# DAC_To_LP_Filter.net
KiCad netlist of a schematic drawn in Altium Designer
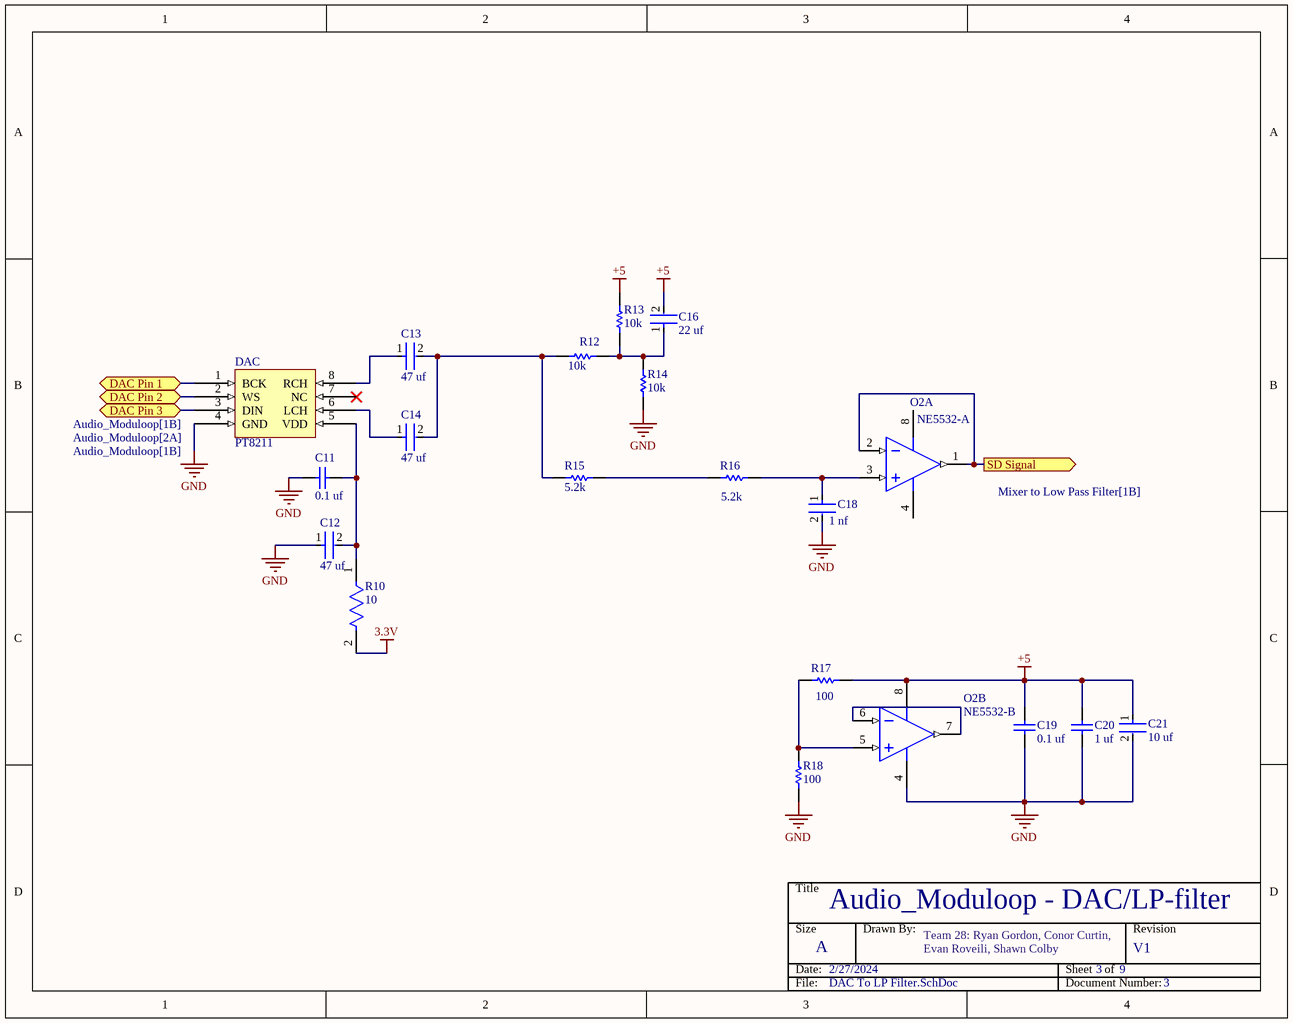
[diagram p0: DAC To LP Filter.SchDoc]

(export (version "E")
  (design (tool "Eeschema 10.0.6"))
  (components
    (comp (ref "C11")
      (value "0.1 uf")
      (footprint "VISH-K104K15X7RF5TL2")
      (description "Ceramic Capacitor, 100 nF, +/- 10%, 50 V, -55 to 125 degC, 2-Pin THD, RoHS, Tape and Reel")
      (fields (field (name "MANUFACTURER") "Vishay") (field (name "TOLERANCE") "±10%"))
      (libsource (lib "Altium Content Vault") (part "CAP-NP-2"))
    )
    (comp (ref "C12")
      (value "47 uf")
      (footprint "FP-RCE2A2-MFG")
      (description "Cap Ceramic 4.7uF 25V X7R ±10% Radial 2.5mm +125°C Automotive Ammo Pack")
      (fields (field (name "TOLERANCE") "10%"))
      (libsource (lib "Altium Content Vault") (part "b4654b650e69147ec39a6b967a45e02"))
    )
    (comp (ref "C13")
      (value "47 uf")
      (footprint "FP-RCE2A2-MFG")
      (description "Cap Ceramic 4.7uF 25V X7R ±10% Radial 2.5mm +125°C Automotive Ammo Pack")
      (fields (field (name "TOLERANCE") "10%"))
      (libsource (lib "Altium Content Vault") (part "b4654b650e69147ec39a6b967a45e02"))
    )
    (comp (ref "C14")
      (value "47 uf")
      (footprint "FP-RCE2A2-MFG")
      (description "Cap Ceramic 4.7uF 25V X7R ±10% Radial 2.5mm +125°C Automotive Ammo Pack")
      (fields (field (name "TOLERANCE") "10%"))
      (libsource (lib "Altium Content Vault") (part "b4654b650e69147ec39a6b967a45e02"))
    )
    (comp (ref "C16")
      (value "22 uf")
      (footprint "FP-RCEWM1-MFG")
      (description "Cap Ceramic 22uF 25V X7R ±20% Radial 5mm +125°C Automotive Ammo Pack")
      (fields (field (name "TOLERANCE") "20%"))
      (libsource (lib "Altium Content Vault") (part "02cd4be3c70576c341d710602a673aa"))
    )
    (comp (ref "C18")
      (value "1 nf")
      (footprint "FP-RCE0DB-MFG")
      (description "Cap Ceramic 470pF 100V X7R ±10% Radial 2.5mm +125°C Ammo Pack")
      (fields (field (name "TOLERANCE") "10%"))
      (libsource (lib "Altium Content Vault") (part "b4654b650e69147ec39a6b967a45e02"))
    )
    (comp (ref "C19")
      (value "0.1 uf")
      (footprint "CAPC2013X135X45ML10T25")
      (description "Chip Capacitor, 0.1 uF, +/- 10%, 50 V, -55 to 125 degC, 0805 (2012 Metric), RoHS, Tape and Reel")
      (fields (field (name "VOLTAGE") "50V") (field (name "TOLERANCE") "10%"))
      (libsource (lib "Altium Content Vault") (part "CAP-NP-2"))
    )
    (comp (ref "C20")
      (value "1 uf")
      (footprint "CAPC2013X145X50LL20T25")
      (fields (field (name "MANUFACTURER") "Kemet") (field (name "PART NUMBER") "C0805C105K4PACTU"))
      (libsource (lib "Altium Content Vault") (part "CAP"))
    )
    (comp (ref "C21")
      (value "10 uf")
      (footprint "FP-C0805C-DG-MFG")
      (description "CAP CER 10UF 10V X5R 0805")
      (fields (field (name "TOLERANCE") "10%") (field (name "MANUFACTURER PART NUMBER") "C0805C106K8PACTU"))
      (libsource (lib "Altium Content Vault") (part "11868f565c42a9108669ba33697ecf6"))
    )
    (comp (ref "DAC")
      (value "PT8211")
      (footprint "SOIC127P602X173-8N")
      (libsource (lib "Ryamgordon") (part "DAC"))
    )
    (comp (ref "O2")
      (value "NE5532-A")
      (footprint "ONSC-SOIC-8-751-07_V")
      (fields (field (name "MANUFACTURER") "On Semiconductor") (field (name "PARTNUMBER") "NE5532AD8R2G"))
      (libsource (lib "Altium Content Vault") (part "ONSC-NE5532-SOIC-8-751-07"))
    )
    (comp (ref "R10")
      (value "10")
      (footprint "FP-RN732A-MFG")
      (description "SMD Chip Resistor, Thin Film, 10Ω, 100 V, 0805 [2012 Metric], 100 mW, 0.1%, RN73 Series")
      (fields
        (field (name "MANUFACTURER") "TE Connectivity")
        (field (name "MANUFACTURER PART NUMBER") "RN73C2A10RBTG")
      )
      (libsource (lib "Altium Content Vault") (part "1029c3af85768c4190bb7ad29bc67b5"))
    )
    (comp (ref "R12")
      (value "10k")
      (footprint "RESC2013X60X35NL10T20")
      (description "Chip Resistor, 10 KOhm, +/- 1%, 0.125 W, -55 to 155 degC, 0805 (2012 Metric), RoHS, Tape and Reel")
      (fields (field (name "MANUFACTURER") "Yageo"))
      (libsource (lib "Altium Content Vault") (part "RES-2"))
    )
    (comp (ref "R13")
      (value "10k")
      (footprint "RESC2013X60X35NL10T20")
      (description "Chip Resistor, 10 KOhm, +/- 1%, 0.125 W, -55 to 155 degC, 0805 (2012 Metric), RoHS, Tape and Reel")
      (fields (field (name "MANUFACTURER") "Yageo"))
      (libsource (lib "Altium Content Vault") (part "RES-2"))
    )
    (comp (ref "R14")
      (value "10k")
      (footprint "RESC2013X60X35NL10T20")
      (description "Chip Resistor, 10 KOhm, +/- 1%, 0.125 W, -55 to 155 degC, 0805 (2012 Metric), RoHS, Tape and Reel")
      (fields (field (name "MANUFACTURER") "Yageo"))
      (libsource (lib "Altium Content Vault") (part "RES-2"))
    )
    (comp (ref "R15")
      (value "5.2k")
      (footprint "RESC2013X70X40LL20T20")
      (fields (field (name "MANUFACTURER") "Panasonic") (field (name "PART NUMBER") "ERJ6ENF6801V"))
      (libsource (lib "Altium Content Vault") (part "RES"))
    )
    (comp (ref "R16")
      (value "5.2k")
      (footprint "RESC2013X70X40LL20T20")
      (fields (field (name "MANUFACTURER") "Panasonic") (field (name "PART NUMBER") "ERJ6ENF6801V"))
      (libsource (lib "Altium Content Vault") (part "RES"))
    )
    (comp (ref "R17")
      (value "100")
      (footprint "RESC2013X60X40ML20T25")
      (fields (field (name "MANUFACTURER") "Panasonic") (field (name "PART NUMBER") "ERA6AEB101V"))
      (libsource (lib "Altium Content Vault") (part "RES"))
    )
    (comp (ref "R18")
      (value "100")
      (footprint "RESC2013X60X40ML20T25")
      (fields (field (name "MANUFACTURER") "Panasonic") (field (name "PART NUMBER") "ERA6AEB101V"))
      (libsource (lib "Altium Content Vault") (part "RES"))
    )
  )
  (nets
    (net (code "1") (name "+5") (class "Default")
      (node (ref "C16") (pin "2") (pinfunction "2_2") (pintype "passive"))
      (node (ref "C19") (pin "1") (pinfunction "1_1") (pintype "passive"))
      (node (ref "C20") (pin "1") (pinfunction "1_1") (pintype "passive"))
      (node (ref "C21") (pin "1") (pinfunction "1_1") (pintype "passive"))
      (node (ref "O2") (pin "8") (pinfunction "V+_8") (pintype "power_in"))
      (node (ref "R13") (pin "1") (pinfunction "1_1") (pintype "passive"))
      (node (ref "R17") (pin "2") (pinfunction "2_2") (pintype "passive"))
    )
    (net (code "2") (name "/DAC Pin 1") (class "Default")
      (node (ref "DAC") (pin "1") (pinfunction "BCK_1") (pintype "input"))
    )
    (net (code "3") (name "/DAC Pin 2") (class "Default")
      (node (ref "DAC") (pin "2") (pinfunction "WS_2") (pintype "input"))
    )
    (net (code "4") (name "/DAC Pin 3") (class "Default")
      (node (ref "DAC") (pin "3") (pinfunction "DIN_3") (pintype "input"))
    )
    (net (code "5") (name "/SD Signal") (class "Default")
      (node (ref "O2") (pin "1") (pinfunction "OUTA_1") (pintype "output"))
      (node (ref "O2") (pin "2") (pinfunction "INA-_2") (pintype "input"))
    )
    (net (code "6") (name "3.3V") (class "Default")
      (node (ref "R10") (pin "2") (pinfunction "2_2") (pintype "passive"))
    )
    (net (code "7") (name "GND") (class "Default")
      (node (ref "C11") (pin "2") (pinfunction "2_2") (pintype "passive"))
      (node (ref "C12") (pin "1") (pinfunction "1_1") (pintype "passive"))
      (node (ref "C18") (pin "2") (pinfunction "2_2") (pintype "passive"))
      (node (ref "C19") (pin "2") (pinfunction "2_2") (pintype "passive"))
      (node (ref "C20") (pin "2") (pinfunction "2_2") (pintype "passive"))
      (node (ref "C21") (pin "2") (pinfunction "2_2") (pintype "passive"))
      (node (ref "DAC") (pin "4") (pinfunction "GND_4") (pintype "input"))
      (node (ref "O2") (pin "4") (pinfunction "V-_4") (pintype "power_in"))
      (node (ref "R14") (pin "2") (pinfunction "2_2") (pintype "passive"))
      (node (ref "R18") (pin "1") (pinfunction "1_1") (pintype "passive"))
    )
    (net (code "8") (name "Net-(C13-Pad2)") (class "Default")
      (node (ref "C13") (pin "2") (pinfunction "2_2") (pintype "passive"))
      (node (ref "C14") (pin "2") (pinfunction "2_2") (pintype "passive"))
      (node (ref "R12") (pin "2") (pinfunction "2_2") (pintype "passive"))
      (node (ref "R15") (pin "1") (pinfunction "1_1") (pintype "passive"))
    )
    (net (code "9") (name "Net-(C16-Pad1)") (class "Default")
      (node (ref "C16") (pin "1") (pinfunction "1_1") (pintype "passive"))
      (node (ref "R12") (pin "1") (pinfunction "1_1") (pintype "passive"))
      (node (ref "R13") (pin "2") (pinfunction "2_2") (pintype "passive"))
      (node (ref "R14") (pin "1") (pinfunction "1_1") (pintype "passive"))
    )
    (net (code "10") (name "Net-(DAC-LCH)") (class "Default")
      (node (ref "C14") (pin "1") (pinfunction "1_1") (pintype "passive"))
      (node (ref "DAC") (pin "6") (pinfunction "LCH_6") (pintype "input"))
    )
    (net (code "11") (name "Net-(DAC-RCH)") (class "Default")
      (node (ref "C13") (pin "1") (pinfunction "1_1") (pintype "passive"))
      (node (ref "DAC") (pin "8") (pinfunction "RCH_8") (pintype "input"))
    )
    (net (code "12") (name "Net-(DAC-VDD)") (class "Default")
      (node (ref "C11") (pin "1") (pinfunction "1_1") (pintype "passive"))
      (node (ref "C12") (pin "2") (pinfunction "2_2") (pintype "passive"))
      (node (ref "DAC") (pin "5") (pinfunction "VDD_5") (pintype "input"))
      (node (ref "R10") (pin "1") (pinfunction "1_1") (pintype "passive"))
    )
    (net (code "13") (name "Net-(O2A-INA+)") (class "Default")
      (node (ref "C18") (pin "1") (pinfunction "1_1") (pintype "passive"))
      (node (ref "O2") (pin "3") (pinfunction "INA+_3") (pintype "input"))
      (node (ref "R16") (pin "2") (pinfunction "2_2") (pintype "passive"))
    )
    (net (code "14") (name "Net-(O2B-INB+)") (class "Default")
      (node (ref "O2") (pin "5") (pinfunction "INB+_5") (pintype "input"))
      (node (ref "R17") (pin "1") (pinfunction "1_1") (pintype "passive"))
      (node (ref "R18") (pin "2") (pinfunction "2_2") (pintype "passive"))
    )
    (net (code "15") (name "Net-(O2B-INB-)") (class "Default")
      (node (ref "O2") (pin "6") (pinfunction "INB-_6") (pintype "input"))
      (node (ref "O2") (pin "7") (pinfunction "OUTB_7") (pintype "output"))
    )
    (net (code "16") (name "Net-(R15-Pad2)") (class "Default")
      (node (ref "R15") (pin "2") (pinfunction "2_2") (pintype "passive"))
      (node (ref "R16") (pin "1") (pinfunction "1_1") (pintype "passive"))
    )
    (net (code "17") (name "unconnected-(DAC-NC-Pad7)") (class "Default")
      (node (ref "DAC") (pin "7") (pinfunction "NC_7") (pintype "input+no_connect"))
    )
    (net (code "18") (name "unconnected-(O2A-V+-Pad8)") (class "Default")
      (node (ref "O2") (pin "8") (pinfunction "V+_8") (pintype "power_in"))
    )
    (net (code "19") (name "unconnected-(O2A-V--Pad4)") (class "Default")
      (node (ref "O2") (pin "4") (pinfunction "V-_4") (pintype "power_in"))
    )
  )
)
